# main.net
KiCad netlist of a schematic drawn in EAGLE
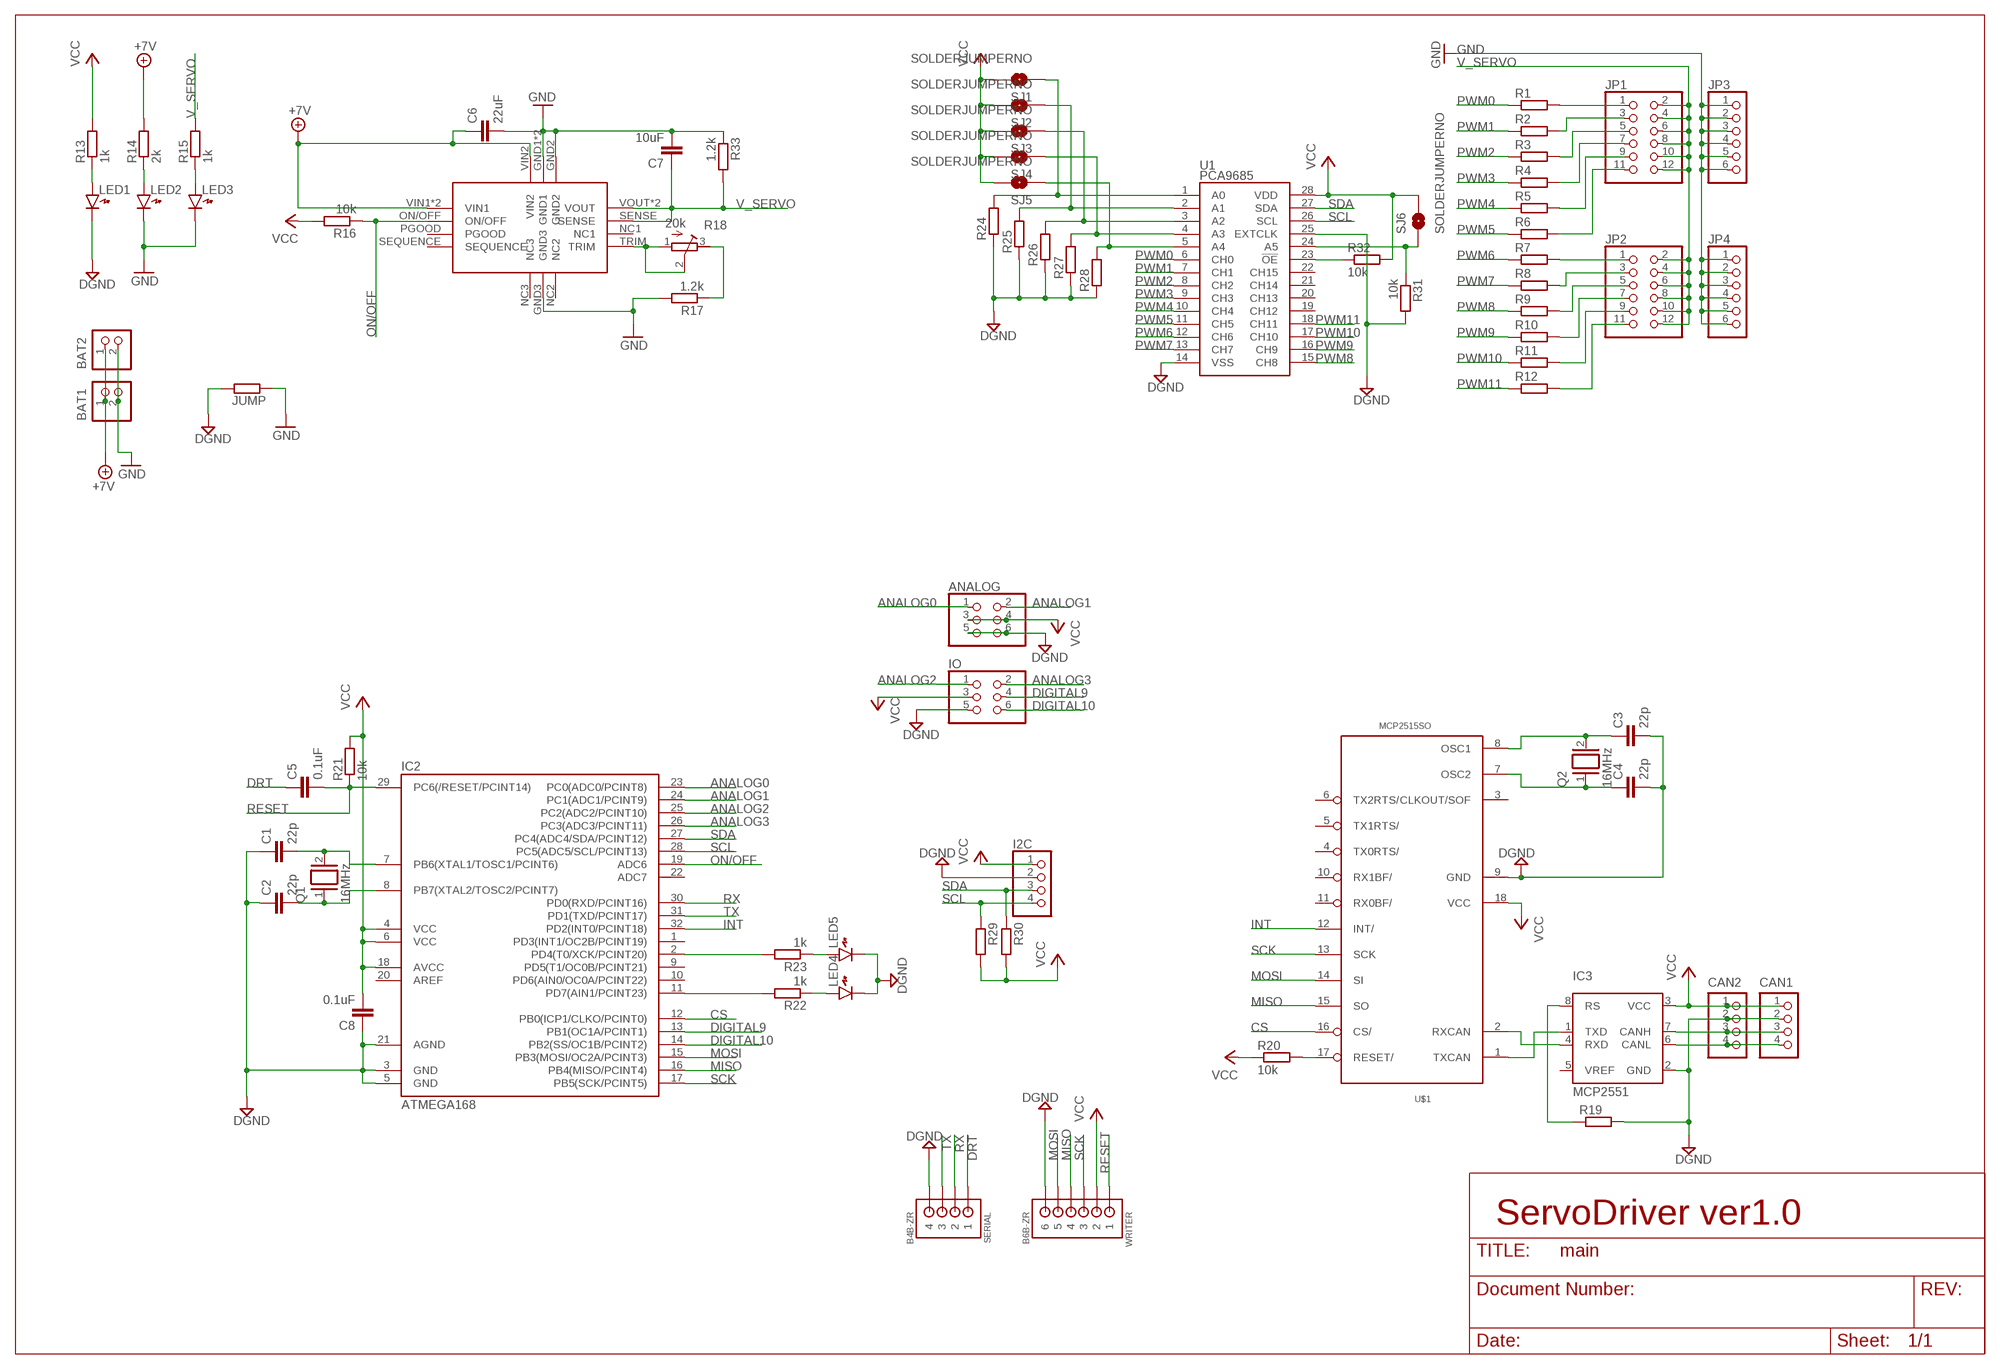
[diagram p0: schematic, sheet 1]

(export (version "E")
  (design (tool "Eeschema 10.0.6"))
  (components
    (comp (ref "ANALOG")
      (value "PINHD-2X3")
      (footprint "eagle-import:2X03")
      (libsource (lib "eagle-import") (part "PINHD-2X3"))
    )
    (comp (ref "BAT1")
      (value "B2P-VH")
      (footprint "eagle-import:B2P-VH")
      (libsource (lib "eagle-import") (part "B2P-VH"))
    )
    (comp (ref "BAT2")
      (value "B2P-VH")
      (footprint "eagle-import:B2P-VH")
      (libsource (lib "eagle-import") (part "B2P-VH"))
    )
    (comp (ref "C1")
      (value "22p")
      (footprint "eagle-import:C2012")
      (libsource (lib "eagle-import") (part "C-EUC2012"))
    )
    (comp (ref "C2")
      (value "22p")
      (footprint "eagle-import:C2012")
      (libsource (lib "eagle-import") (part "C-EUC2012"))
    )
    (comp (ref "C3")
      (value "22p")
      (footprint "eagle-import:C2012")
      (libsource (lib "eagle-import") (part "C-EUC2012"))
    )
    (comp (ref "C4")
      (value "22p")
      (footprint "eagle-import:C2012")
      (libsource (lib "eagle-import") (part "C-EUC2012"))
    )
    (comp (ref "C5")
      (value "0.1uF")
      (footprint "eagle-import:C2012")
      (libsource (lib "eagle-import") (part "C-EUC2012"))
    )
    (comp (ref "C6")
      (value "22uF")
      (footprint "eagle-import:C2012")
      (libsource (lib "eagle-import") (part "C-EUC2012"))
    )
    (comp (ref "C7")
      (value "10uF")
      (footprint "eagle-import:C2012")
      (libsource (lib "eagle-import") (part "C-EUC2012"))
    )
    (comp (ref "C8")
      (value "0.1uF")
      (footprint "eagle-import:C2012")
      (libsource (lib "eagle-import") (part "C-EUC2012"))
    )
    (comp (ref "CAN1")
      (value "B4B-PH-K-S")
      (footprint "eagle-import:B4B-PH-K-S")
      (libsource (lib "eagle-import") (part "B4B-PH-K-S"))
    )
    (comp (ref "CAN2")
      (value "B4B-PH-K-S")
      (footprint "eagle-import:B4B-PH-K-S")
      (libsource (lib "eagle-import") (part "B4B-PH-K-S"))
    )
    (comp (ref "I2C")
      (value "PINHD-1X4")
      (footprint "eagle-import:1X04")
      (libsource (lib "eagle-import") (part "PINHD-1X4"))
    )
    (comp (ref "IC1")
      (value "OKL-T")
      (footprint "eagle-import:OKL-T")
      (libsource (lib "eagle-import") (part "OKL-T"))
    )
    (comp (ref "IC2")
      (value "ATMEGA168")
      (footprint "eagle-import:TQFP32-08")
      (libsource (lib "eagle-import") (part "ATMEGA48/88/168-AU"))
    )
    (comp (ref "IC3")
      (value "MCP2551")
      (footprint "eagle-import:SOIC")
      (libsource (lib "eagle-import") (part "MCP2551"))
    )
    (comp (ref "IO")
      (value "PINHD-2X3")
      (footprint "eagle-import:2X03")
      (libsource (lib "eagle-import") (part "PINHD-2X3"))
    )
    (comp (ref "JP1")
      (value "PINHD-2X6")
      (footprint "eagle-import:2X06")
      (libsource (lib "eagle-import") (part "PINHD-2X6"))
    )
    (comp (ref "JP2")
      (value "PINHD-2X6")
      (footprint "eagle-import:2X06")
      (libsource (lib "eagle-import") (part "PINHD-2X6"))
    )
    (comp (ref "JP3")
      (value "PINHD-1X6")
      (footprint "eagle-import:1X06")
      (libsource (lib "eagle-import") (part "PINHD-1X6"))
    )
    (comp (ref "JP4")
      (value "PINHD-1X6")
      (footprint "eagle-import:1X06")
      (libsource (lib "eagle-import") (part "PINHD-1X6"))
    )
    (comp (ref "JUMP")
      (value "R-EU_M2012")
      (footprint "eagle-import:M2012")
      (libsource (lib "eagle-import") (part "R-EU_M2012"))
    )
    (comp (ref "LED1")
      (value "LED2012")
      (footprint "eagle-import:LED2012")
      (libsource (lib "eagle-import") (part "LED2012"))
    )
    (comp (ref "LED2")
      (value "LED2012")
      (footprint "eagle-import:LED2012")
      (libsource (lib "eagle-import") (part "LED2012"))
    )
    (comp (ref "LED3")
      (value "LED2012")
      (footprint "eagle-import:LED2012")
      (libsource (lib "eagle-import") (part "LED2012"))
    )
    (comp (ref "LED4")
      (value "LED2012")
      (footprint "eagle-import:LED2012")
      (libsource (lib "eagle-import") (part "LED2012"))
    )
    (comp (ref "LED5")
      (value "LED2012")
      (footprint "eagle-import:LED2012")
      (libsource (lib "eagle-import") (part "LED2012"))
    )
    (comp (ref "Q1")
      (value "16MHz")
      (footprint "eagle-import:QS")
      (libsource (lib "eagle-import") (part "XTAL/S"))
    )
    (comp (ref "Q2")
      (value "16MHz")
      (footprint "eagle-import:QS")
      (libsource (lib "eagle-import") (part "XTAL/S"))
    )
    (comp (ref "R1")
      (value "R-EU_M2012")
      (footprint "eagle-import:M2012")
      (libsource (lib "eagle-import") (part "R-EU_M2012"))
    )
    (comp (ref "R2")
      (value "R-EU_M2012")
      (footprint "eagle-import:M2012")
      (libsource (lib "eagle-import") (part "R-EU_M2012"))
    )
    (comp (ref "R3")
      (value "R-EU_M2012")
      (footprint "eagle-import:M2012")
      (libsource (lib "eagle-import") (part "R-EU_M2012"))
    )
    (comp (ref "R4")
      (value "R-EU_M2012")
      (footprint "eagle-import:M2012")
      (libsource (lib "eagle-import") (part "R-EU_M2012"))
    )
    (comp (ref "R5")
      (value "R-EU_M2012")
      (footprint "eagle-import:M2012")
      (libsource (lib "eagle-import") (part "R-EU_M2012"))
    )
    (comp (ref "R6")
      (value "R-EU_M2012")
      (footprint "eagle-import:M2012")
      (libsource (lib "eagle-import") (part "R-EU_M2012"))
    )
    (comp (ref "R7")
      (value "R-EU_M2012")
      (footprint "eagle-import:M2012")
      (libsource (lib "eagle-import") (part "R-EU_M2012"))
    )
    (comp (ref "R8")
      (value "R-EU_M2012")
      (footprint "eagle-import:M2012")
      (libsource (lib "eagle-import") (part "R-EU_M2012"))
    )
    (comp (ref "R9")
      (value "R-EU_M2012")
      (footprint "eagle-import:M2012")
      (libsource (lib "eagle-import") (part "R-EU_M2012"))
    )
    (comp (ref "R10")
      (value "R-EU_M2012")
      (footprint "eagle-import:M2012")
      (libsource (lib "eagle-import") (part "R-EU_M2012"))
    )
    (comp (ref "R11")
      (value "R-EU_M2012")
      (footprint "eagle-import:M2012")
      (libsource (lib "eagle-import") (part "R-EU_M2012"))
    )
    (comp (ref "R12")
      (value "R-EU_M2012")
      (footprint "eagle-import:M2012")
      (libsource (lib "eagle-import") (part "R-EU_M2012"))
    )
    (comp (ref "R13")
      (value "1k")
      (footprint "eagle-import:M2012")
      (libsource (lib "eagle-import") (part "R-EU_M2012"))
    )
    (comp (ref "R14")
      (value "2k")
      (footprint "eagle-import:M2012")
      (libsource (lib "eagle-import") (part "R-EU_M2012"))
    )
    (comp (ref "R15")
      (value "1k")
      (footprint "eagle-import:M2012")
      (libsource (lib "eagle-import") (part "R-EU_M2012"))
    )
    (comp (ref "R16")
      (value "10k")
      (footprint "eagle-import:M2012")
      (libsource (lib "eagle-import") (part "R-EU_M2012"))
    )
    (comp (ref "R17")
      (value "1.2k")
      (footprint "eagle-import:M2012")
      (libsource (lib "eagle-import") (part "R-EU_M2012"))
    )
    (comp (ref "R18")
      (value "20k")
      (footprint "eagle-import:RTRIM64W")
      (libsource (lib "eagle-import") (part "R-TRIMM64W"))
    )
    (comp (ref "R19")
      (value "R-EU_M2012")
      (footprint "eagle-import:M2012")
      (libsource (lib "eagle-import") (part "R-EU_M2012"))
    )
    (comp (ref "R20")
      (value "10k")
      (footprint "eagle-import:M2012")
      (libsource (lib "eagle-import") (part "R-EU_M2012"))
    )
    (comp (ref "R21")
      (value "10k")
      (footprint "eagle-import:M2012")
      (libsource (lib "eagle-import") (part "R-EU_M2012"))
    )
    (comp (ref "R22")
      (value "1k")
      (footprint "eagle-import:M2012")
      (libsource (lib "eagle-import") (part "R-EU_M2012"))
    )
    (comp (ref "R23")
      (value "1k")
      (footprint "eagle-import:M2012")
      (libsource (lib "eagle-import") (part "R-EU_M2012"))
    )
    (comp (ref "R24")
      (value "R-EU_M2012")
      (footprint "eagle-import:M2012")
      (libsource (lib "eagle-import") (part "R-EU_M2012"))
    )
    (comp (ref "R25")
      (value "R-EU_M2012")
      (footprint "eagle-import:M2012")
      (libsource (lib "eagle-import") (part "R-EU_M2012"))
    )
    (comp (ref "R26")
      (value "R-EU_M2012")
      (footprint "eagle-import:M2012")
      (libsource (lib "eagle-import") (part "R-EU_M2012"))
    )
    (comp (ref "R27")
      (value "R-EU_M2012")
      (footprint "eagle-import:M2012")
      (libsource (lib "eagle-import") (part "R-EU_M2012"))
    )
    (comp (ref "R28")
      (value "R-EU_M2012")
      (footprint "eagle-import:M2012")
      (libsource (lib "eagle-import") (part "R-EU_M2012"))
    )
    (comp (ref "R29")
      (value "R-EU_M2012")
      (footprint "eagle-import:M2012")
      (libsource (lib "eagle-import") (part "R-EU_M2012"))
    )
    (comp (ref "R30")
      (value "R-EU_M2012")
      (footprint "eagle-import:M2012")
      (libsource (lib "eagle-import") (part "R-EU_M2012"))
    )
    (comp (ref "R31")
      (value "10k")
      (footprint "eagle-import:M2012")
      (libsource (lib "eagle-import") (part "R-EU_M2012"))
    )
    (comp (ref "R32")
      (value "10k")
      (footprint "eagle-import:M2012")
      (libsource (lib "eagle-import") (part "R-EU_M2012"))
    )
    (comp (ref "R33")
      (value "1.2k")
      (footprint "eagle-import:M2012")
      (libsource (lib "eagle-import") (part "R-EU_M2012"))
    )
    (comp (ref "SERIAL")
      (value "B4B-ZR")
      (footprint "eagle-import:B4B-ZR")
      (libsource (lib "eagle-import") (part "B4B-ZR"))
    )
    (comp (ref "SJ1")
      (value "SOLDERJUMPERNO")
      (footprint "eagle-import:SJ_2S-NO")
      (libsource (lib "eagle-import") (part "SOLDERJUMPERNO"))
    )
    (comp (ref "SJ2")
      (value "SOLDERJUMPERNO")
      (footprint "eagle-import:SJ_2S-NO")
      (libsource (lib "eagle-import") (part "SOLDERJUMPERNO"))
    )
    (comp (ref "SJ3")
      (value "SOLDERJUMPERNO")
      (footprint "eagle-import:SJ_2S-NO")
      (libsource (lib "eagle-import") (part "SOLDERJUMPERNO"))
    )
    (comp (ref "SJ4")
      (value "SOLDERJUMPERNO")
      (footprint "eagle-import:SJ_2S-NO")
      (libsource (lib "eagle-import") (part "SOLDERJUMPERNO"))
    )
    (comp (ref "SJ5")
      (value "SOLDERJUMPERNO")
      (footprint "eagle-import:SJ_2S-NO")
      (libsource (lib "eagle-import") (part "SOLDERJUMPERNO"))
    )
    (comp (ref "SJ6")
      (value "SOLDERJUMPERNO")
      (footprint "eagle-import:SJ_2S-NO")
      (libsource (lib "eagle-import") (part "SOLDERJUMPERNO"))
    )
    (comp (ref "U$1")
      (value "MCP2515SO")
      (footprint "eagle-import:SO18L")
      (libsource (lib "eagle-import") (part "MCP2515SO"))
    )
    (comp (ref "U1")
      (value "PCA9685")
      (footprint "eagle-import:TSSOP-28_4MM")
      (libsource (lib "eagle-import") (part "PCA9685"))
    )
    (comp (ref "WRITER")
      (value "B6B-ZR")
      (footprint "eagle-import:B6B-ZR")
      (libsource (lib "eagle-import") (part "B6B-ZR"))
    )
  )
  (nets
    (net (code "1") (name "+7V") (class "Default")
      (node (ref "BAT1") (pin "1") (pinfunction "1_1") (pintype "passive"))
      (node (ref "BAT2") (pin "1") (pinfunction "1_1") (pintype "passive"))
      (node (ref "C6") (pin "1") (pinfunction "1_1") (pintype "passive"))
      (node (ref "IC1") (pin "VIN1") (pinfunction "VIN1_VIN1") (pintype "bidirectional"))
      (node (ref "IC1") (pin "VIN2") (pinfunction "VIN2_VIN2") (pintype "bidirectional"))
      (node (ref "IC1") (pin "VIN_BRIDGE") (pinfunction "VIN1_VIN_BRIDGE") (pintype "bidirectional"))
      (node (ref "R14") (pin "2") (pinfunction "2_2") (pintype "passive"))
    )
    (net (code "2") (name "/ANALOG0") (class "Default")
      (node (ref "ANALOG") (pin "1") (pinfunction "1_1") (pintype "passive"))
      (node (ref "IC2") (pin "23") (pinfunction "PC0(ADC0/PCINT8)_23") (pintype "bidirectional"))
    )
    (net (code "3") (name "/ANALOG1") (class "Default")
      (node (ref "ANALOG") (pin "2") (pinfunction "2_2") (pintype "passive"))
      (node (ref "IC2") (pin "24") (pinfunction "PC1(ADC1/PCINT9)_24") (pintype "bidirectional"))
    )
    (net (code "4") (name "/ANALOG2") (class "Default")
      (node (ref "IC2") (pin "25") (pinfunction "PC2(ADC2/PCINT10)_25") (pintype "bidirectional"))
      (node (ref "IO") (pin "1") (pinfunction "1_1") (pintype "passive"))
    )
    (net (code "5") (name "/ANALOG3") (class "Default")
      (node (ref "IC2") (pin "26") (pinfunction "PC3(ADC3/PCINT11)_26") (pintype "bidirectional"))
      (node (ref "IO") (pin "2") (pinfunction "2_2") (pintype "passive"))
    )
    (net (code "6") (name "/CS") (class "Default")
      (node (ref "IC2") (pin "12") (pinfunction "PB0(ICP1/CLKO/PCINT0)_12") (pintype "bidirectional"))
      (node (ref "U$1") (pin "16") (pinfunction "CS/_16") (pintype "input"))
    )
    (net (code "7") (name "/DIGITAL9") (class "Default")
      (node (ref "IC2") (pin "13") (pinfunction "PB1(OC1A/PCINT1)_13") (pintype "bidirectional"))
      (node (ref "IO") (pin "4") (pinfunction "4_4") (pintype "passive"))
    )
    (net (code "8") (name "/DIGITAL10") (class "Default")
      (node (ref "IC2") (pin "14") (pinfunction "PB2(SS/OC1B/PCINT2)_14") (pintype "bidirectional"))
      (node (ref "IO") (pin "6") (pinfunction "6_6") (pintype "passive"))
    )
    (net (code "9") (name "/DRT") (class "Default")
      (node (ref "C5") (pin "1") (pinfunction "1_1") (pintype "passive"))
      (node (ref "SERIAL") (pin "1") (pinfunction "1_1") (pintype "bidirectional"))
    )
    (net (code "10") (name "/INT") (class "Default")
      (node (ref "IC2") (pin "32") (pinfunction "PD2(INT0/PCINT18)_32") (pintype "bidirectional"))
      (node (ref "U$1") (pin "12") (pinfunction "INT/_12") (pintype "output"))
    )
    (net (code "11") (name "/MISO") (class "Default")
      (node (ref "IC2") (pin "16") (pinfunction "PB4(MISO/PCINT4)_16") (pintype "bidirectional"))
      (node (ref "U$1") (pin "15") (pinfunction "SO_15") (pintype "output"))
      (node (ref "WRITER") (pin "4") (pinfunction "4_4") (pintype "bidirectional"))
    )
    (net (code "12") (name "/MOSI") (class "Default")
      (node (ref "IC2") (pin "15") (pinfunction "PB3(MOSI/OC2A/PCINT3)_15") (pintype "bidirectional"))
      (node (ref "U$1") (pin "14") (pinfunction "SI_14") (pintype "input"))
      (node (ref "WRITER") (pin "5") (pinfunction "5_5") (pintype "bidirectional"))
    )
    (net (code "13") (name "/ON{slash}OFF") (class "Default")
      (node (ref "IC1") (pin "ON/OFF") (pinfunction "ON/OFF_ON/OFF") (pintype "bidirectional"))
      (node (ref "IC2") (pin "19") (pinfunction "ADC6_19") (pintype "passive"))
      (node (ref "R16") (pin "1") (pinfunction "1_1") (pintype "passive"))
    )
    (net (code "14") (name "/PWM0") (class "Default")
      (node (ref "R1") (pin "1") (pinfunction "1_1") (pintype "passive"))
      (node (ref "U1") (pin "6") (pinfunction "CH0_6") (pintype "bidirectional"))
    )
    (net (code "15") (name "/PWM1") (class "Default")
      (node (ref "R2") (pin "1") (pinfunction "1_1") (pintype "passive"))
      (node (ref "U1") (pin "7") (pinfunction "CH1_7") (pintype "bidirectional"))
    )
    (net (code "16") (name "/PWM2") (class "Default")
      (node (ref "R3") (pin "1") (pinfunction "1_1") (pintype "passive"))
      (node (ref "U1") (pin "8") (pinfunction "CH2_8") (pintype "bidirectional"))
    )
    (net (code "17") (name "/PWM3") (class "Default")
      (node (ref "R4") (pin "1") (pinfunction "1_1") (pintype "passive"))
      (node (ref "U1") (pin "9") (pinfunction "CH3_9") (pintype "bidirectional"))
    )
    (net (code "18") (name "/PWM4") (class "Default")
      (node (ref "R5") (pin "1") (pinfunction "1_1") (pintype "passive"))
      (node (ref "U1") (pin "10") (pinfunction "CH4_10") (pintype "bidirectional"))
    )
    (net (code "19") (name "/PWM5") (class "Default")
      (node (ref "R6") (pin "1") (pinfunction "1_1") (pintype "passive"))
      (node (ref "U1") (pin "11") (pinfunction "CH5_11") (pintype "bidirectional"))
    )
    (net (code "20") (name "/PWM6") (class "Default")
      (node (ref "R7") (pin "1") (pinfunction "1_1") (pintype "passive"))
      (node (ref "U1") (pin "12") (pinfunction "CH6_12") (pintype "bidirectional"))
    )
    (net (code "21") (name "/PWM7") (class "Default")
      (node (ref "R8") (pin "1") (pinfunction "1_1") (pintype "passive"))
      (node (ref "U1") (pin "13") (pinfunction "CH7_13") (pintype "bidirectional"))
    )
    (net (code "22") (name "/PWM8") (class "Default")
      (node (ref "R9") (pin "1") (pinfunction "1_1") (pintype "passive"))
      (node (ref "U1") (pin "15") (pinfunction "CH8_15") (pintype "bidirectional"))
    )
    (net (code "23") (name "/PWM9") (class "Default")
      (node (ref "R10") (pin "1") (pinfunction "1_1") (pintype "passive"))
      (node (ref "U1") (pin "16") (pinfunction "CH9_16") (pintype "bidirectional"))
    )
    (net (code "24") (name "/PWM10") (class "Default")
      (node (ref "R11") (pin "1") (pinfunction "1_1") (pintype "passive"))
      (node (ref "U1") (pin "17") (pinfunction "CH10_17") (pintype "bidirectional"))
    )
    (net (code "25") (name "/PWM11") (class "Default")
      (node (ref "R12") (pin "1") (pinfunction "1_1") (pintype "passive"))
      (node (ref "U1") (pin "18") (pinfunction "CH11_18") (pintype "bidirectional"))
    )
    (net (code "26") (name "/RESET") (class "Default")
      (node (ref "C5") (pin "2") (pinfunction "2_2") (pintype "passive"))
      (node (ref "IC2") (pin "29") (pinfunction "PC6(/RESET/PCINT14)_29") (pintype "bidirectional"))
      (node (ref "R21") (pin "1") (pinfunction "1_1") (pintype "passive"))
      (node (ref "WRITER") (pin "1") (pinfunction "1_1") (pintype "bidirectional"))
    )
    (net (code "27") (name "/RX") (class "Default")
      (node (ref "IC2") (pin "30") (pinfunction "PD0(RXD/PCINT16)_30") (pintype "bidirectional"))
      (node (ref "SERIAL") (pin "2") (pinfunction "2_2") (pintype "bidirectional"))
    )
    (net (code "28") (name "/SCK") (class "Default")
      (node (ref "IC2") (pin "17") (pinfunction "PB5(SCK/PCINT5)_17") (pintype "bidirectional"))
      (node (ref "U$1") (pin "13") (pinfunction "SCK_13") (pintype "input"))
      (node (ref "WRITER") (pin "3") (pinfunction "3_3") (pintype "bidirectional"))
    )
    (net (code "29") (name "/SCL") (class "Default")
      (node (ref "I2C") (pin "4") (pinfunction "4_4") (pintype "passive"))
      (node (ref "IC2") (pin "28") (pinfunction "PC5(ADC5/SCL/PCINT13)_28") (pintype "bidirectional"))
      (node (ref "R29") (pin "1") (pinfunction "1_1") (pintype "passive"))
      (node (ref "U1") (pin "26") (pinfunction "SCL_26") (pintype "bidirectional"))
    )
    (net (code "30") (name "/SDA") (class "Default")
      (node (ref "I2C") (pin "3") (pinfunction "3_3") (pintype "passive"))
      (node (ref "IC2") (pin "27") (pinfunction "PC4(ADC4/SDA/PCINT12)_27") (pintype "bidirectional"))
      (node (ref "R30") (pin "1") (pinfunction "1_1") (pintype "passive"))
      (node (ref "U1") (pin "27") (pinfunction "SDA_27") (pintype "bidirectional"))
    )
    (net (code "31") (name "/TX") (class "Default")
      (node (ref "IC2") (pin "31") (pinfunction "PD1(TXD/PCINT17)_31") (pintype "bidirectional"))
      (node (ref "SERIAL") (pin "3") (pinfunction "3_3") (pintype "bidirectional"))
    )
    (net (code "32") (name "/V_SERVO") (class "Default")
      (node (ref "C7") (pin "1") (pinfunction "1_1") (pintype "passive"))
      (node (ref "IC1") (pin "SENSE") (pinfunction "SENSE_SENSE") (pintype "bidirectional"))
      (node (ref "IC1") (pin "VOUT") (pinfunction "VOUT_VOUT") (pintype "bidirectional"))
      (node (ref "IC1") (pin "VOUT_BRIDGE") (pinfunction "VOUT_VOUT_BRIDGE") (pintype "bidirectional"))
      (node (ref "JP1") (pin "10") (pinfunction "10_10") (pintype "passive"))
      (node (ref "JP1") (pin "12") (pinfunction "12_12") (pintype "passive"))
      (node (ref "JP1") (pin "2") (pinfunction "2_2") (pintype "passive"))
      (node (ref "JP1") (pin "4") (pinfunction "4_4") (pintype "passive"))
      (node (ref "JP1") (pin "6") (pinfunction "6_6") (pintype "passive"))
      (node (ref "JP1") (pin "8") (pinfunction "8_8") (pintype "passive"))
      (node (ref "JP2") (pin "10") (pinfunction "10_10") (pintype "passive"))
      (node (ref "JP2") (pin "12") (pinfunction "12_12") (pintype "passive"))
      (node (ref "JP2") (pin "2") (pinfunction "2_2") (pintype "passive"))
      (node (ref "JP2") (pin "4") (pinfunction "4_4") (pintype "passive"))
      (node (ref "JP2") (pin "6") (pinfunction "6_6") (pintype "passive"))
      (node (ref "JP2") (pin "8") (pinfunction "8_8") (pintype "passive"))
      (node (ref "R15") (pin "2") (pinfunction "2_2") (pintype "passive"))
      (node (ref "R33") (pin "2") (pinfunction "2_2") (pintype "passive"))
    )
    (net (code "33") (name "DGND") (class "Default")
      (node (ref "ANALOG") (pin "5") (pinfunction "5_5") (pintype "passive"))
      (node (ref "ANALOG") (pin "6") (pinfunction "6_6") (pintype "passive"))
      (node (ref "C1") (pin "1") (pinfunction "1_1") (pintype "passive"))
      (node (ref "C2") (pin "1") (pinfunction "1_1") (pintype "passive"))
      (node (ref "C3") (pin "2") (pinfunction "2_2") (pintype "passive"))
      (node (ref "C4") (pin "2") (pinfunction "2_2") (pintype "passive"))
      (node (ref "C8") (pin "1") (pinfunction "1_1") (pintype "passive"))
      (node (ref "CAN1") (pin "2") (pinfunction "2_2") (pintype "passive"))
      (node (ref "CAN2") (pin "2") (pinfunction "2_2") (pintype "passive"))
      (node (ref "I2C") (pin "2") (pinfunction "2_2") (pintype "passive"))
      (node (ref "IC2") (pin "21") (pinfunction "AGND_21") (pintype "power_in"))
      (node (ref "IC2") (pin "3") (pinfunction "GND_3") (pintype "power_in"))
      (node (ref "IC2") (pin "5") (pinfunction "GND_5") (pintype "power_in"))
      (node (ref "IC3") (pin "2") (pinfunction "GND_2") (pintype "power_in"))
      (node (ref "IO") (pin "5") (pinfunction "5_5") (pintype "passive"))
      (node (ref "JUMP") (pin "2") (pinfunction "2_2") (pintype "passive"))
      (node (ref "LED1") (pin "K") (pinfunction "K_K") (pintype "passive"))
      (node (ref "LED4") (pin "K") (pinfunction "K_K") (pintype "passive"))
      (node (ref "LED5") (pin "K") (pinfunction "K_K") (pintype "passive"))
      (node (ref "R19") (pin "2") (pinfunction "2_2") (pintype "passive"))
      (node (ref "R24") (pin "1") (pinfunction "1_1") (pintype "passive"))
      (node (ref "R25") (pin "1") (pinfunction "1_1") (pintype "passive"))
      (node (ref "R26") (pin "1") (pinfunction "1_1") (pintype "passive"))
      (node (ref "R27") (pin "1") (pinfunction "1_1") (pintype "passive"))
      (node (ref "R28") (pin "1") (pinfunction "1_1") (pintype "passive"))
      (node (ref "R31") (pin "2") (pinfunction "2_2") (pintype "passive"))
      (node (ref "SERIAL") (pin "4") (pinfunction "4_4") (pintype "bidirectional"))
      (node (ref "U$1") (pin "9") (pinfunction "GND_9") (pintype "power_in"))
      (node (ref "U1") (pin "14") (pinfunction "VSS_14") (pintype "bidirectional"))
      (node (ref "U1") (pin "25") (pinfunction "EXTCLK_25") (pintype "bidirectional"))
      (node (ref "WRITER") (pin "6") (pinfunction "6_6") (pintype "bidirectional"))
    )
    (net (code "34") (name "GND") (class "Default")
      (node (ref "BAT1") (pin "2") (pinfunction "2_2") (pintype "passive"))
      (node (ref "BAT2") (pin "2") (pinfunction "2_2") (pintype "passive"))
      (node (ref "C6") (pin "2") (pinfunction "2_2") (pintype "passive"))
      (node (ref "C7") (pin "2") (pinfunction "2_2") (pintype "passive"))
      (node (ref "IC1") (pin "GND1") (pinfunction "GND1_GND1") (pintype "bidirectional"))
      (node (ref "IC1") (pin "GND2") (pinfunction "GND2_GND2") (pintype "bidirectional"))
      (node (ref "IC1") (pin "GND3") (pinfunction "GND3_GND3") (pintype "bidirectional"))
      (node (ref "IC1") (pin "GND_BRIDGE") (pinfunction "GND1_GND_BRIDGE") (pintype "bidirectional"))
      (node (ref "JP3") (pin "1") (pinfunction "1_1") (pintype "passive"))
      (node (ref "JP3") (pin "2") (pinfunction "2_2") (pintype "passive"))
      (node (ref "JP3") (pin "3") (pinfunction "3_3") (pintype "passive"))
      (node (ref "JP3") (pin "4") (pinfunction "4_4") (pintype "passive"))
      (node (ref "JP3") (pin "5") (pinfunction "5_5") (pintype "passive"))
      (node (ref "JP3") (pin "6") (pinfunction "6_6") (pintype "passive"))
      (node (ref "JP4") (pin "1") (pinfunction "1_1") (pintype "passive"))
      (node (ref "JP4") (pin "2") (pinfunction "2_2") (pintype "passive"))
      (node (ref "JP4") (pin "3") (pinfunction "3_3") (pintype "passive"))
      (node (ref "JP4") (pin "4") (pinfunction "4_4") (pintype "passive"))
      (node (ref "JP4") (pin "5") (pinfunction "5_5") (pintype "passive"))
      (node (ref "JP4") (pin "6") (pinfunction "6_6") (pintype "passive"))
      (node (ref "JUMP") (pin "1") (pinfunction "1_1") (pintype "passive"))
      (node (ref "LED2") (pin "K") (pinfunction "K_K") (pintype "passive"))
      (node (ref "LED3") (pin "K") (pinfunction "K_K") (pintype "passive"))
      (node (ref "R17") (pin "2") (pinfunction "2_2") (pintype "passive"))
      (node (ref "R33") (pin "1") (pinfunction "1_1") (pintype "passive"))
    )
    (net (code "35") (name "Net-(IC2-PB6(XTAL1{slash}TOSC1{slash}PCINT6))") (class "Default")
      (node (ref "C1") (pin "2") (pinfunction "2_2") (pintype "passive"))
      (node (ref "IC2") (pin "7") (pinfunction "PB6(XTAL1/TOSC1/PCINT6)_7") (pintype "bidirectional"))
      (node (ref "Q1") (pin "2") (pinfunction "2_2") (pintype "passive"))
    )
    (net (code "36") (name "Net-(IC2-PB7(XTAL2{slash}TOSC2{slash}PCINT7))") (class "Default")
      (node (ref "C2") (pin "2") (pinfunction "2_2") (pintype "passive"))
      (node (ref "IC2") (pin "8") (pinfunction "PB7(XTAL2/TOSC2/PCINT7)_8") (pintype "bidirectional"))
      (node (ref "Q1") (pin "1") (pinfunction "1_1") (pintype "passive"))
    )
    (net (code "37") (name "Net-(IC2-PD4(T0{slash}XCK{slash}PCINT20))") (class "Default")
      (node (ref "IC2") (pin "2") (pinfunction "PD4(T0/XCK/PCINT20)_2") (pintype "bidirectional"))
      (node (ref "R23") (pin "2") (pinfunction "2_2") (pintype "passive"))
    )
    (net (code "38") (name "Net-(IC2-PD7(AIN1{slash}PCINT23))") (class "Default")
      (node (ref "IC2") (pin "11") (pinfunction "PD7(AIN1/PCINT23)_11") (pintype "bidirectional"))
      (node (ref "R22") (pin "2") (pinfunction "2_2") (pintype "passive"))
    )
    (net (code "39") (name "Net-(IC3-CANH)") (class "Default")
      (node (ref "CAN1") (pin "3") (pinfunction "3_3") (pintype "passive"))
      (node (ref "CAN2") (pin "3") (pinfunction "3_3") (pintype "passive"))
      (node (ref "IC3") (pin "7") (pinfunction "CANH_7") (pintype "bidirectional"))
    )
    (net (code "40") (name "Net-(IC3-CANL)") (class "Default")
      (node (ref "CAN1") (pin "4") (pinfunction "4_4") (pintype "passive"))
      (node (ref "CAN2") (pin "4") (pinfunction "4_4") (pintype "passive"))
      (node (ref "IC3") (pin "6") (pinfunction "CANL_6") (pintype "bidirectional"))
    )
    (net (code "41") (name "Net-(IC3-RS)") (class "Default")
      (node (ref "IC3") (pin "8") (pinfunction "RS_8") (pintype "bidirectional"))
      (node (ref "R19") (pin "1") (pinfunction "1_1") (pintype "passive"))
    )
    (net (code "42") (name "Net-(IC3-RXD)") (class "Default")
      (node (ref "IC3") (pin "4") (pinfunction "RXD_4") (pintype "bidirectional"))
      (node (ref "U$1") (pin "2") (pinfunction "RXCAN_2") (pintype "input"))
    )
    (net (code "43") (name "Net-(IC3-TXD)") (class "Default")
      (node (ref "IC3") (pin "1") (pinfunction "TXD_1") (pintype "bidirectional"))
      (node (ref "U$1") (pin "1") (pinfunction "TXCAN_1") (pintype "output"))
    )
    (net (code "44") (name "Net-(JP1-Pad1)") (class "Default")
      (node (ref "JP1") (pin "1") (pinfunction "1_1") (pintype "passive"))
      (node (ref "R1") (pin "2") (pinfunction "2_2") (pintype "passive"))
    )
    (net (code "45") (name "Net-(JP1-Pad3)") (class "Default")
      (node (ref "JP1") (pin "3") (pinfunction "3_3") (pintype "passive"))
      (node (ref "R2") (pin "2") (pinfunction "2_2") (pintype "passive"))
    )
    (net (code "46") (name "Net-(JP1-Pad5)") (class "Default")
      (node (ref "JP1") (pin "5") (pinfunction "5_5") (pintype "passive"))
      (node (ref "R3") (pin "2") (pinfunction "2_2") (pintype "passive"))
    )
    (net (code "47") (name "Net-(JP1-Pad7)") (class "Default")
      (node (ref "JP1") (pin "7") (pinfunction "7_7") (pintype "passive"))
      (node (ref "R4") (pin "2") (pinfunction "2_2") (pintype "passive"))
    )
    (net (code "48") (name "Net-(JP1-Pad9)") (class "Default")
      (node (ref "JP1") (pin "9") (pinfunction "9_9") (pintype "passive"))
      (node (ref "R5") (pin "2") (pinfunction "2_2") (pintype "passive"))
    )
    (net (code "49") (name "Net-(JP1-Pad11)") (class "Default")
      (node (ref "JP1") (pin "11") (pinfunction "11_11") (pintype "passive"))
      (node (ref "R6") (pin "2") (pinfunction "2_2") (pintype "passive"))
    )
    (net (code "50") (name "Net-(JP2-Pad1)") (class "Default")
      (node (ref "JP2") (pin "1") (pinfunction "1_1") (pintype "passive"))
      (node (ref "R7") (pin "2") (pinfunction "2_2") (pintype "passive"))
    )
    (net (code "51") (name "Net-(JP2-Pad3)") (class "Default")
      (node (ref "JP2") (pin "3") (pinfunction "3_3") (pintype "passive"))
      (node (ref "R8") (pin "2") (pinfunction "2_2") (pintype "passive"))
    )
    (net (code "52") (name "Net-(JP2-Pad5)") (class "Default")
      (node (ref "JP2") (pin "5") (pinfunction "5_5") (pintype "passive"))
      (node (ref "R9") (pin "2") (pinfunction "2_2") (pintype "passive"))
    )
    (net (code "53") (name "Net-(JP2-Pad7)") (class "Default")
      (node (ref "JP2") (pin "7") (pinfunction "7_7") (pintype "passive"))
      (node (ref "R10") (pin "2") (pinfunction "2_2") (pintype "passive"))
    )
    (net (code "54") (name "Net-(JP2-Pad9)") (class "Default")
      (node (ref "JP2") (pin "9") (pinfunction "9_9") (pintype "passive"))
      (node (ref "R11") (pin "2") (pinfunction "2_2") (pintype "passive"))
    )
    (net (code "55") (name "Net-(JP2-Pad11)") (class "Default")
      (node (ref "JP2") (pin "11") (pinfunction "11_11") (pintype "passive"))
      (node (ref "R12") (pin "2") (pinfunction "2_2") (pintype "passive"))
    )
    (net (code "56") (name "Net-(LED1-PadA)") (class "Default")
      (node (ref "LED1") (pin "A") (pinfunction "A_A") (pintype "passive"))
      (node (ref "R13") (pin "1") (pinfunction "1_1") (pintype "passive"))
    )
    (net (code "57") (name "Net-(LED2-PadA)") (class "Default")
      (node (ref "LED2") (pin "A") (pinfunction "A_A") (pintype "passive"))
      (node (ref "R14") (pin "1") (pinfunction "1_1") (pintype "passive"))
    )
    (net (code "58") (name "Net-(LED3-PadA)") (class "Default")
      (node (ref "LED3") (pin "A") (pinfunction "A_A") (pintype "passive"))
      (node (ref "R15") (pin "1") (pinfunction "1_1") (pintype "passive"))
    )
    (net (code "59") (name "Net-(LED4-PadA)") (class "Default")
      (node (ref "LED4") (pin "A") (pinfunction "A_A") (pintype "passive"))
      (node (ref "R22") (pin "1") (pinfunction "1_1") (pintype "passive"))
    )
    (net (code "60") (name "Net-(LED5-PadA)") (class "Default")
      (node (ref "LED5") (pin "A") (pinfunction "A_A") (pintype "passive"))
      (node (ref "R23") (pin "1") (pinfunction "1_1") (pintype "passive"))
    )
    (net (code "61") (name "Net-(R18-A)") (class "Default")
      (node (ref "IC1") (pin "TRIM") (pinfunction "TRIM_TRIM") (pintype "bidirectional"))
      (node (ref "R18") (pin "1") (pinfunction "A_1") (pintype "passive"))
      (node (ref "R18") (pin "2") (pinfunction "S_2") (pintype "passive"))
    )
    (net (code "62") (name "Net-(R18-E)") (class "Default")
      (node (ref "R17") (pin "1") (pinfunction "1_1") (pintype "passive"))
      (node (ref "R18") (pin "3") (pinfunction "E_3") (pintype "passive"))
    )
    (net (code "63") (name "Net-(U$1-OSC1)") (class "Default")
      (node (ref "C3") (pin "1") (pinfunction "1_1") (pintype "passive"))
      (node (ref "Q2") (pin "2") (pinfunction "2_2") (pintype "passive"))
      (node (ref "U$1") (pin "8") (pinfunction "OSC1_8") (pintype "bidirectional"))
    )
    (net (code "64") (name "Net-(U$1-OSC2)") (class "Default")
      (node (ref "C4") (pin "1") (pinfunction "1_1") (pintype "passive"))
      (node (ref "Q2") (pin "1") (pinfunction "1_1") (pintype "passive"))
      (node (ref "U$1") (pin "7") (pinfunction "OSC2_7") (pintype "bidirectional"))
    )
    (net (code "65") (name "Net-(U$1-RESET{slash})") (class "Default")
      (node (ref "R20") (pin "2") (pinfunction "2_2") (pintype "passive"))
      (node (ref "U$1") (pin "17") (pinfunction "RESET/_17") (pintype "input"))
    )
    (net (code "66") (name "Net-(U1-A0)") (class "Default")
      (node (ref "R24") (pin "2") (pinfunction "2_2") (pintype "passive"))
      (node (ref "SJ1") (pin "1") (pinfunction "1_1") (pintype "passive"))
      (node (ref "U1") (pin "1") (pinfunction "A0_1") (pintype "bidirectional"))
    )
    (net (code "67") (name "Net-(U1-A1)") (class "Default")
      (node (ref "R25") (pin "2") (pinfunction "2_2") (pintype "passive"))
      (node (ref "SJ2") (pin "1") (pinfunction "1_1") (pintype "passive"))
      (node (ref "U1") (pin "2") (pinfunction "A1_2") (pintype "bidirectional"))
    )
    (net (code "68") (name "Net-(U1-A2)") (class "Default")
      (node (ref "R26") (pin "2") (pinfunction "2_2") (pintype "passive"))
      (node (ref "SJ3") (pin "1") (pinfunction "1_1") (pintype "passive"))
      (node (ref "U1") (pin "3") (pinfunction "A2_3") (pintype "bidirectional"))
    )
    (net (code "69") (name "Net-(U1-A3)") (class "Default")
      (node (ref "R27") (pin "2") (pinfunction "2_2") (pintype "passive"))
      (node (ref "SJ4") (pin "1") (pinfunction "1_1") (pintype "passive"))
      (node (ref "U1") (pin "4") (pinfunction "A3_4") (pintype "bidirectional"))
    )
    (net (code "70") (name "Net-(U1-A4)") (class "Default")
      (node (ref "R28") (pin "2") (pinfunction "2_2") (pintype "passive"))
      (node (ref "SJ5") (pin "1") (pinfunction "1_1") (pintype "passive"))
      (node (ref "U1") (pin "5") (pinfunction "A4_5") (pintype "bidirectional"))
    )
    (net (code "71") (name "Net-(U1-A5)") (class "Default")
      (node (ref "R31") (pin "1") (pinfunction "1_1") (pintype "passive"))
      (node (ref "SJ6") (pin "1") (pinfunction "1_1") (pintype "passive"))
      (node (ref "U1") (pin "24") (pinfunction "A5_24") (pintype "bidirectional"))
    )
    (net (code "72") (name "Net-(U1-~{OE})") (class "Default")
      (node (ref "R32") (pin "1") (pinfunction "1_1") (pintype "passive"))
      (node (ref "U1") (pin "23") (pinfunction "~{OE}_23") (pintype "bidirectional"))
    )
    (net (code "73") (name "VCC") (class "Default")
      (node (ref "ANALOG") (pin "3") (pinfunction "3_3") (pintype "passive"))
      (node (ref "ANALOG") (pin "4") (pinfunction "4_4") (pintype "passive"))
      (node (ref "C8") (pin "2") (pinfunction "2_2") (pintype "passive"))
      (node (ref "CAN1") (pin "1") (pinfunction "1_1") (pintype "passive"))
      (node (ref "CAN2") (pin "1") (pinfunction "1_1") (pintype "passive"))
      (node (ref "I2C") (pin "1") (pinfunction "1_1") (pintype "passive"))
      (node (ref "IC2") (pin "18") (pinfunction "AVCC_18") (pintype "passive"))
      (node (ref "IC2") (pin "4") (pinfunction "VCC_4") (pintype "power_in"))
      (node (ref "IC2") (pin "6") (pinfunction "VCC_6") (pintype "power_in"))
      (node (ref "IC3") (pin "3") (pinfunction "VCC_3") (pintype "power_in"))
      (node (ref "IO") (pin "3") (pinfunction "3_3") (pintype "passive"))
      (node (ref "R13") (pin "2") (pinfunction "2_2") (pintype "passive"))
      (node (ref "R16") (pin "2") (pinfunction "2_2") (pintype "passive"))
      (node (ref "R20") (pin "1") (pinfunction "1_1") (pintype "passive"))
      (node (ref "R21") (pin "2") (pinfunction "2_2") (pintype "passive"))
      (node (ref "R29") (pin "2") (pinfunction "2_2") (pintype "passive"))
      (node (ref "R30") (pin "2") (pinfunction "2_2") (pintype "passive"))
      (node (ref "R32") (pin "2") (pinfunction "2_2") (pintype "passive"))
      (node (ref "SJ1") (pin "2") (pinfunction "2_2") (pintype "passive"))
      (node (ref "SJ2") (pin "2") (pinfunction "2_2") (pintype "passive"))
      (node (ref "SJ3") (pin "2") (pinfunction "2_2") (pintype "passive"))
      (node (ref "SJ4") (pin "2") (pinfunction "2_2") (pintype "passive"))
      (node (ref "SJ5") (pin "2") (pinfunction "2_2") (pintype "passive"))
      (node (ref "SJ6") (pin "2") (pinfunction "2_2") (pintype "passive"))
      (node (ref "U$1") (pin "18") (pinfunction "VCC_18") (pintype "power_in"))
      (node (ref "U1") (pin "28") (pinfunction "VDD_28") (pintype "bidirectional"))
      (node (ref "WRITER") (pin "2") (pinfunction "2_2") (pintype "bidirectional"))
    )
    (net (code "74") (name "unconnected-(IC1-PadNC1)") (class "Default")
      (node (ref "IC1") (pin "NC1") (pinfunction "NC1_NC1") (pintype "bidirectional"))
    )
    (net (code "75") (name "unconnected-(IC1-PadNC2)") (class "Default")
      (node (ref "IC1") (pin "NC2") (pinfunction "NC2_NC2") (pintype "bidirectional"))
    )
    (net (code "76") (name "unconnected-(IC1-PadNC3)") (class "Default")
      (node (ref "IC1") (pin "NC3") (pinfunction "NC3_NC3") (pintype "bidirectional"))
    )
    (net (code "77") (name "unconnected-(IC1-PadPGOOD)") (class "Default")
      (node (ref "IC1") (pin "PGOOD") (pinfunction "PGOOD_PGOOD") (pintype "bidirectional"))
    )
    (net (code "78") (name "unconnected-(IC1-PadSEQUENCE)") (class "Default")
      (node (ref "IC1") (pin "SEQUENCE") (pinfunction "SEQUENCE_SEQUENCE") (pintype "bidirectional"))
    )
    (net (code "79") (name "unconnected-(IC2-ADC7-Pad22)") (class "Default")
      (node (ref "IC2") (pin "22") (pinfunction "ADC7_22") (pintype "passive"))
    )
    (net (code "80") (name "unconnected-(IC2-AREF-Pad20)") (class "Default")
      (node (ref "IC2") (pin "20") (pinfunction "AREF_20") (pintype "passive"))
    )
    (net (code "81") (name "unconnected-(IC2-PD3(INT1{slash}OC2B{slash}PCINT19)-Pad1)") (class "Default")
      (node (ref "IC2") (pin "1") (pinfunction "PD3(INT1/OC2B/PCINT19)_1") (pintype "bidirectional"))
    )
    (net (code "82") (name "unconnected-(IC2-PD5(T1{slash}OC0B{slash}PCINT21)-Pad9)") (class "Default")
      (node (ref "IC2") (pin "9") (pinfunction "PD5(T1/OC0B/PCINT21)_9") (pintype "bidirectional"))
    )
    (net (code "83") (name "unconnected-(IC2-PD6(AIN0{slash}OC0A{slash}PCINT22)-Pad10)") (class "Default")
      (node (ref "IC2") (pin "10") (pinfunction "PD6(AIN0/OC0A/PCINT22)_10") (pintype "bidirectional"))
    )
    (net (code "84") (name "unconnected-(IC3-VREF-Pad5)") (class "Default")
      (node (ref "IC3") (pin "5") (pinfunction "VREF_5") (pintype "bidirectional"))
    )
    (net (code "85") (name "unconnected-(U$1-CLKOUT{slash}SOF-Pad3)") (class "Default")
      (node (ref "U$1") (pin "3") (pinfunction "CLKOUT/SOF_3") (pintype "bidirectional"))
    )
    (net (code "86") (name "unconnected-(U$1-RX0BF{slash}-Pad11)") (class "Default")
      (node (ref "U$1") (pin "11") (pinfunction "RX0BF/_11") (pintype "bidirectional"))
    )
    (net (code "87") (name "unconnected-(U$1-RX1BF{slash}-Pad10)") (class "Default")
      (node (ref "U$1") (pin "10") (pinfunction "RX1BF/_10") (pintype "bidirectional"))
    )
    (net (code "88") (name "unconnected-(U$1-TX0RTS{slash}-Pad4)") (class "Default")
      (node (ref "U$1") (pin "4") (pinfunction "TX0RTS/_4") (pintype "bidirectional"))
    )
    (net (code "89") (name "unconnected-(U$1-TX1RTS{slash}-Pad5)") (class "Default")
      (node (ref "U$1") (pin "5") (pinfunction "TX1RTS/_5") (pintype "bidirectional"))
    )
    (net (code "90") (name "unconnected-(U$1-TX2RTS{slash}-Pad6)") (class "Default")
      (node (ref "U$1") (pin "6") (pinfunction "TX2RTS/_6") (pintype "bidirectional"))
    )
    (net (code "91") (name "unconnected-(U1-CH12-Pad19)") (class "Default")
      (node (ref "U1") (pin "19") (pinfunction "CH12_19") (pintype "bidirectional"))
    )
    (net (code "92") (name "unconnected-(U1-CH13-Pad20)") (class "Default")
      (node (ref "U1") (pin "20") (pinfunction "CH13_20") (pintype "bidirectional"))
    )
    (net (code "93") (name "unconnected-(U1-CH14-Pad21)") (class "Default")
      (node (ref "U1") (pin "21") (pinfunction "CH14_21") (pintype "bidirectional"))
    )
    (net (code "94") (name "unconnected-(U1-CH15-Pad22)") (class "Default")
      (node (ref "U1") (pin "22") (pinfunction "CH15_22") (pintype "bidirectional"))
    )
  )
)
